# ProProject_PetCareSTM32_MiniSTM32_2024-0.net
KiCad netlist of a schematic drawn in EasyEDA Pro
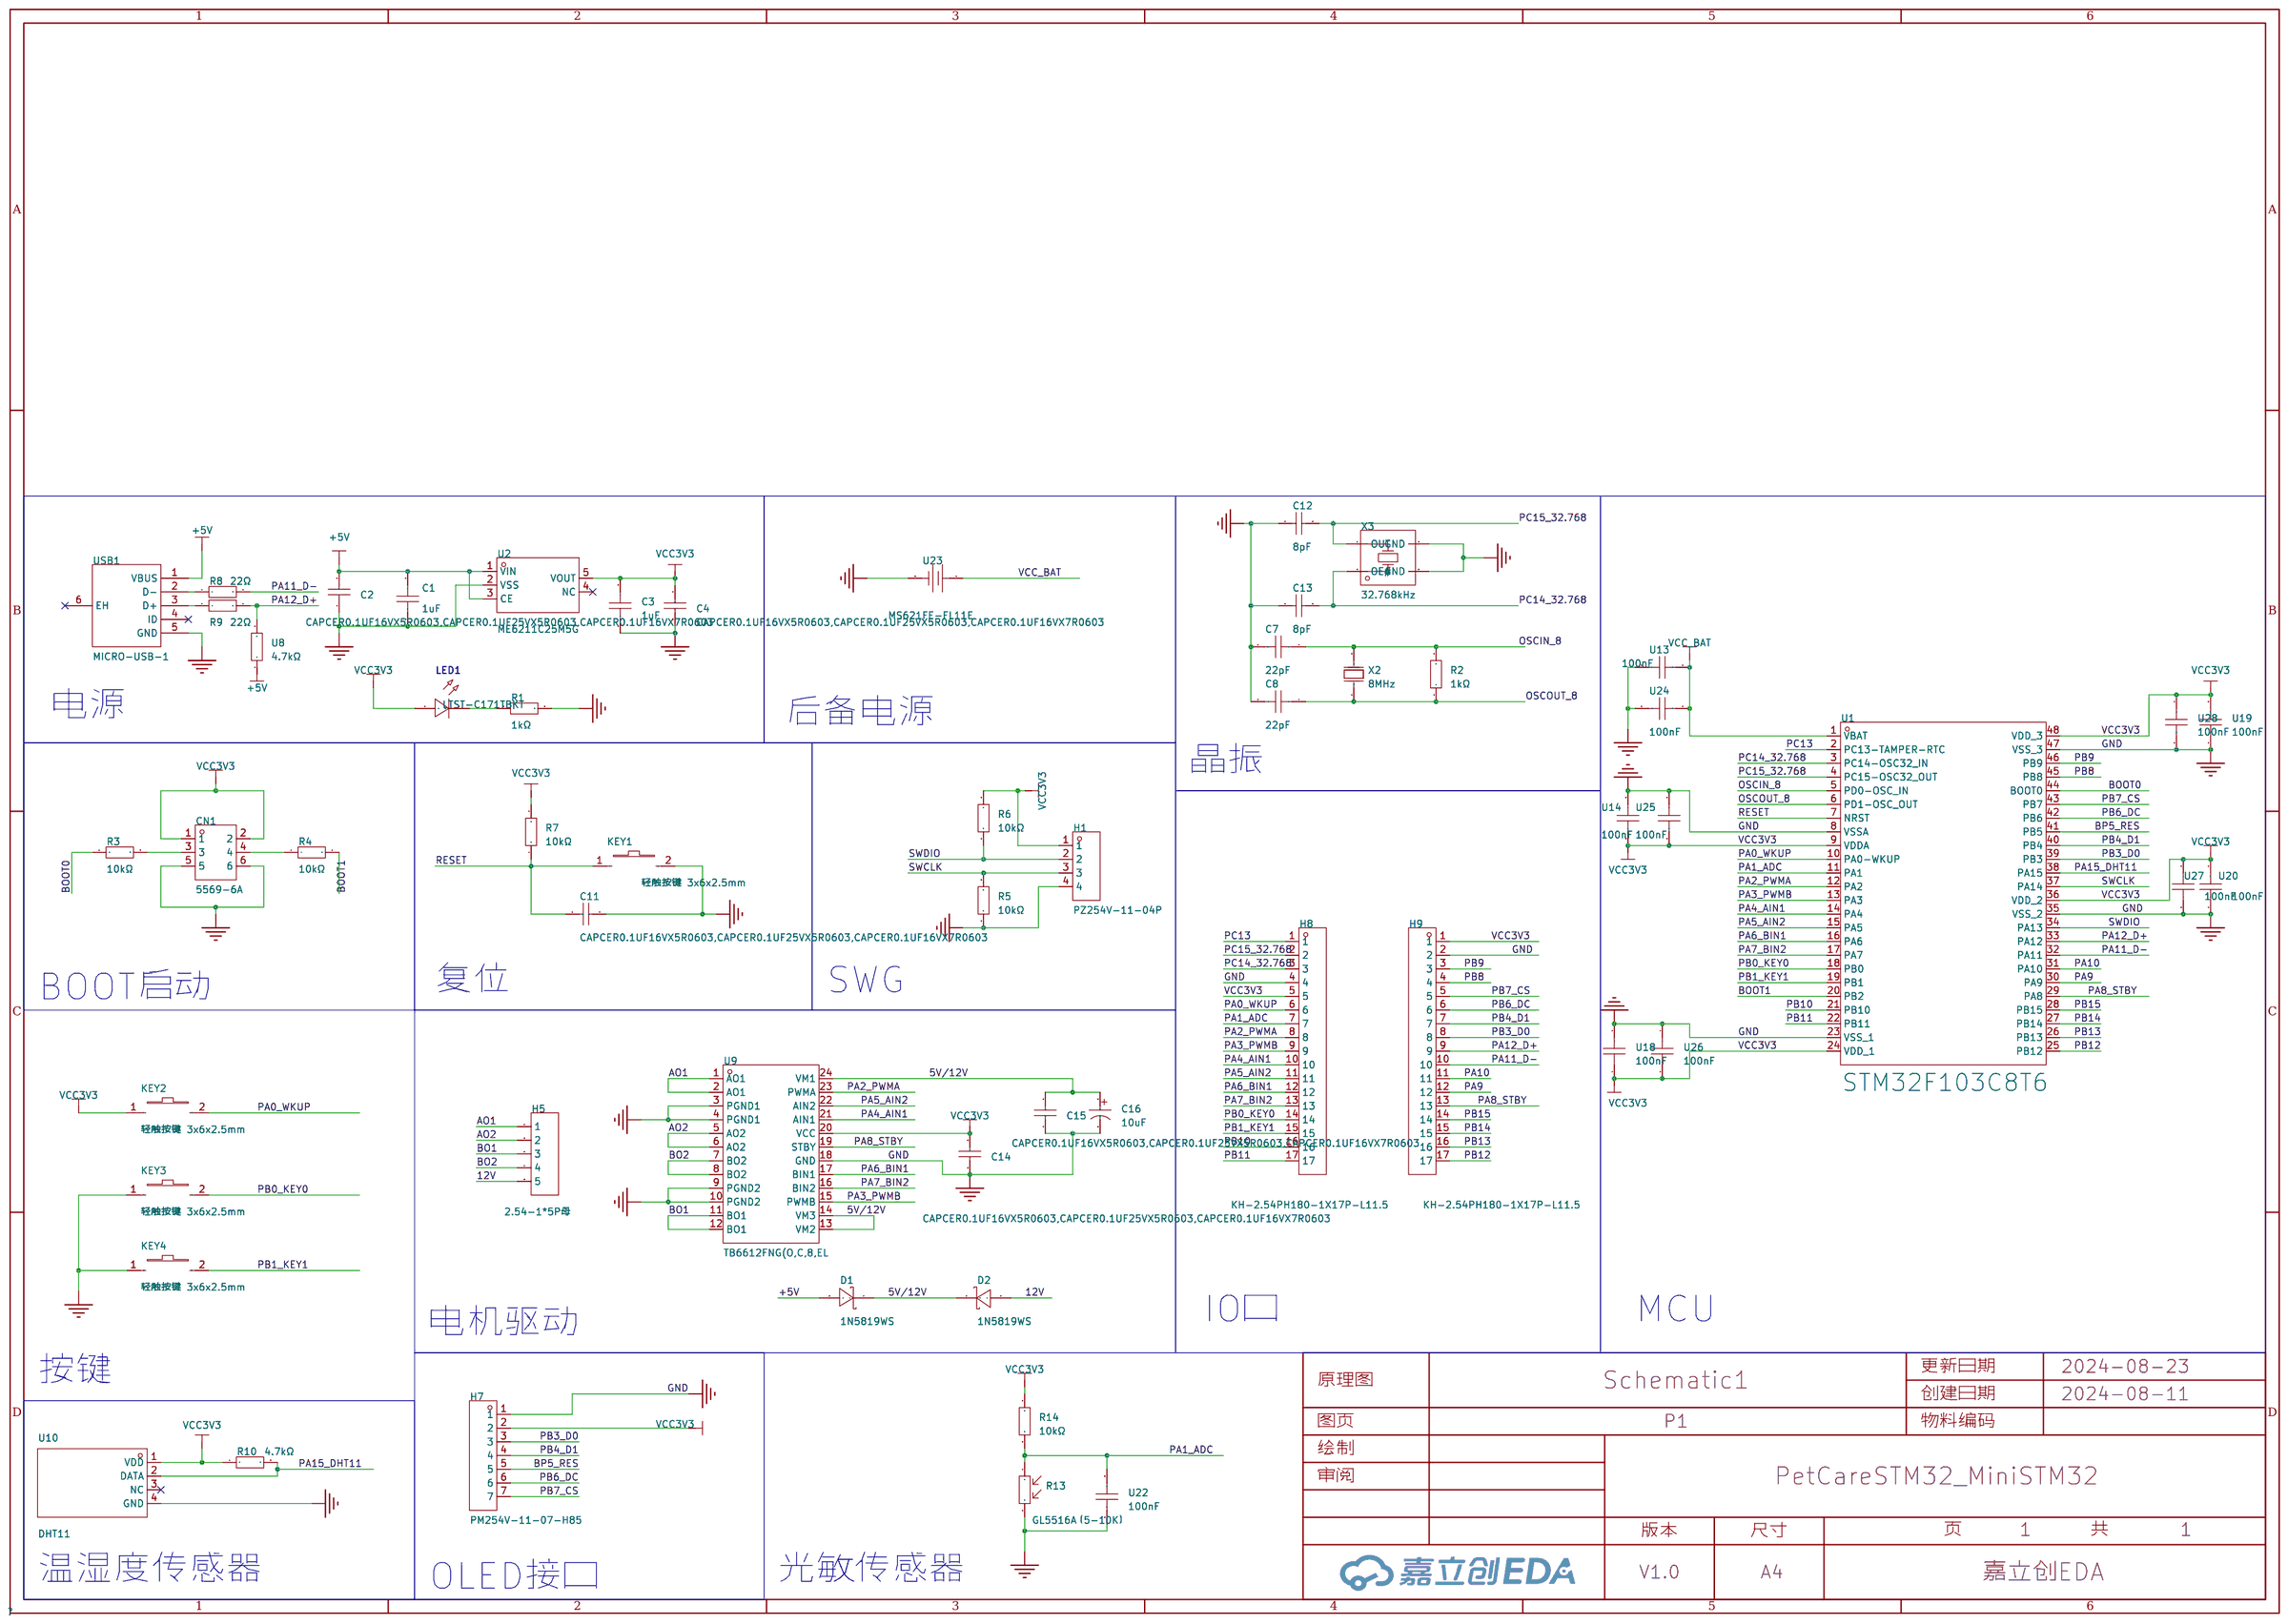
[diagram p0: schematic sheet]

(export (version "E")
  (design (tool "Eeschema 10.0.6"))
  (components
    (comp (ref "C1")
      (value "1uF")
      (footprint "easyedapro:C0603")
      (description "容值:1uF;精度:±10%;额定电压:50V;材质(温度系数):X5R;")
      (fields
        (field (name "Manufacturer Part") "CL10A105KB8NNNC")
        (field (name "Manufacturer") "SAMSUNG(三星)")
      )
      (libsource (lib "easyedapro") (part "CL10A105KB8NNNC"))
    )
    (comp (ref "C2")
      (value "CAPCER0.1UF16VX5R0603,CAPCER0.1UF25VX5R0603,CAPCER0.1UF16VX7R0603")
      (footprint "easyedapro:C0603")
      (libsource (lib "easyedapro") (part "CAPCER0.1UF16VX5R0603,CAPCER0.1UF25VX5R0603,CAPCER0.1UF16VX7R0603"))
    )
    (comp (ref "C3")
      (value "1uF")
      (footprint "easyedapro:C0603")
      (description "容值:1uF;精度:±10%;额定电压:50V;材质(温度系数):X5R;")
      (fields
        (field (name "Manufacturer Part") "CL10A105KB8NNNC")
        (field (name "Manufacturer") "SAMSUNG(三星)")
      )
      (libsource (lib "easyedapro") (part "CL10A105KB8NNNC"))
    )
    (comp (ref "C4")
      (value "CAPCER0.1UF16VX5R0603,CAPCER0.1UF25VX5R0603,CAPCER0.1UF16VX7R0603")
      (footprint "easyedapro:C0603")
      (libsource (lib "easyedapro") (part "CAPCER0.1UF16VX5R0603,CAPCER0.1UF25VX5R0603,CAPCER0.1UF16VX7R0603"))
    )
    (comp (ref "C7")
      (value "22pF")
      (footprint "easyedapro:C0603")
      (description "容值:22pF;精度:±5%;额定电压:50V;材质(温度系数):C0G;")
      (fields
        (field (name "Manufacturer Part") "CL10C220JB81PNC")
        (field (name "Manufacturer") "SAMSUNG(三星)")
      )
      (libsource (lib "easyedapro") (part "CL10C220JB81PNC"))
    )
    (comp (ref "C8")
      (value "22pF")
      (footprint "easyedapro:C0603")
      (description "容值:22pF;精度:±5%;额定电压:50V;材质(温度系数):C0G;")
      (fields
        (field (name "Manufacturer Part") "CL10C220JB81PNC")
        (field (name "Manufacturer") "SAMSUNG(三星)")
      )
      (libsource (lib "easyedapro") (part "CL10C220JB81PNC"))
    )
    (comp (ref "C11")
      (value "CAPCER0.1UF16VX5R0603,CAPCER0.1UF25VX5R0603,CAPCER0.1UF16VX7R0603")
      (footprint "easyedapro:C0603")
      (libsource (lib "easyedapro") (part "CAPCER0.1UF16VX5R0603,CAPCER0.1UF25VX5R0603,CAPCER0.1UF16VX7R0603"))
    )
    (comp (ref "C12")
      (value "8pF")
      (footprint "easyedapro:C0603")
      (description "容值:8pF;额定电压:50V;材质(温度系数):C0G;")
      (fields (field (name "Manufacturer Part") "0603CG8R0C500NT") (field (name "Manufacturer") "FH(风华)"))
      (libsource (lib "easyedapro") (part "0603CG8R0C500NT_C36508"))
    )
    (comp (ref "C13")
      (value "8pF")
      (footprint "easyedapro:C0603")
      (description "容值:8pF;额定电压:50V;材质(温度系数):C0G;")
      (fields (field (name "Manufacturer Part") "0603CG8R0C500NT") (field (name "Manufacturer") "FH(风华)"))
      (libsource (lib "easyedapro") (part "0603CG8R0C500NT_C36508"))
    )
    (comp (ref "C14")
      (value "CAPCER0.1UF16VX5R0603,CAPCER0.1UF25VX5R0603,CAPCER0.1UF16VX7R0603")
      (footprint "easyedapro:C0603")
      (libsource (lib "easyedapro") (part "CAPCER0.1UF16VX5R0603,CAPCER0.1UF25VX5R0603,CAPCER0.1UF16VX7R0603"))
    )
    (comp (ref "C15")
      (value "CAPCER0.1UF16VX5R0603,CAPCER0.1UF25VX5R0603,CAPCER0.1UF16VX7R0603")
      (footprint "easyedapro:C0603")
      (libsource (lib "easyedapro") (part "CAPCER0.1UF16VX5R0603,CAPCER0.1UF25VX5R0603,CAPCER0.1UF16VX7R0603"))
    )
    (comp (ref "C16")
      (value "10uF")
      (footprint "easyedapro:CAP-TH_BD5.0-P2.00-D0.8-FD")
      (description "容值:10uF;精度:±20%;额定电压:25V;")
      (fields (field (name "Manufacturer Part") "KF100M025C110A") (field (name "Manufacturer") "CapXon(丰宾)"))
      (libsource (lib "easyedapro") (part "KF100M025C110A"))
    )
    (comp (ref "CN1")
      (value "5569-6A")
      (footprint "easyedapro:CONN-TH_6P-P4.20_5569-6A-1")
      (libsource (lib "easyedapro") (part "5569-6A"))
    )
    (comp (ref "D1")
      (value "1N5819WS")
      (footprint "easyedapro:SOD-323_L1.8-W1.3-LS2.5-RD")
      (description "正向压降(Vf):600mV@1A;直流反向耐压(Vr):40V;平均整流电流(Io):1A;")
      (fields (field (name "Manufacturer") "Hottech(合科泰)"))
      (libsource (lib "easyedapro") (part "1N5819WS"))
    )
    (comp (ref "D2")
      (value "1N5819WS")
      (footprint "easyedapro:SOD-323_L1.8-W1.3-LS2.5-RD")
      (description "正向压降(Vf):600mV@1A;直流反向耐压(Vr):40V;平均整流电流(Io):1A;")
      (fields (field (name "Manufacturer") "Hottech(合科泰)"))
      (libsource (lib "easyedapro") (part "1N5819WS"))
    )
    (comp (ref "H1")
      (value "PZ254V-11-04P")
      (footprint "easyedapro:HDR-TH_4P-P2.54-V-M")
      (fields (field (name "Manufacturer") "XFCN(兴飞)"))
      (libsource (lib "easyedapro") (part "PZ254V-11-04P_C2691448"))
    )
    (comp (ref "H5")
      (value "2.54-1*5P母")
      (footprint "easyedapro:HDR-TH_5P-P2.54-V-F")
      (description "插孔结构:1x5P;间距:2.54mm;行距:-;安装类型:直插;排数:单排;总孔位数:5P;塑高:-;触头材质:-;触头镀层:-;")
      (fields (field (name "Manufacturer") "BOOMELE(博穆精密)"))
      (libsource (lib "easyedapro") (part "Header-Female-2.54_1x5"))
    )
    (comp (ref "H7")
      (value "PM254V-11-07-H85")
      (footprint "easyedapro:HDR-TH_7P-P2.54-V-F")
      (fields (field (name "Manufacturer") "XFCN(兴飞)"))
      (libsource (lib "easyedapro") (part "PM254V-11-07-H85"))
    )
    (comp (ref "H8")
      (value "KH-2.54PH180-1X17P-L11.5")
      (footprint "easyedapro:HDR-TH_17P-P2.54-V-M")
      (fields (field (name "Manufacturer") "kinghelm(金航标)"))
      (libsource (lib "easyedapro") (part "KH-2.54PH180-1X17P-L11.5"))
    )
    (comp (ref "H9")
      (value "KH-2.54PH180-1X17P-L11.5")
      (footprint "easyedapro:HDR-TH_17P-P2.54-V-M")
      (fields (field (name "Manufacturer") "kinghelm(金航标)"))
      (libsource (lib "easyedapro") (part "KH-2.54PH180-1X17P-L11.5"))
    )
    (comp (ref "KEY1")
      (value "轻触按键 3x6x2.5mm")
      (footprint "easyedapro:SW-SMD_L6.0-W3.6-LS8.0")
      (libsource (lib "easyedapro") (part "3x6x2.5mm"))
    )
    (comp (ref "KEY2")
      (value "轻触按键 3x6x2.5mm")
      (footprint "easyedapro:SW-SMD_L6.0-W3.6-LS8.0")
      (libsource (lib "easyedapro") (part "3x6x2.5mm"))
    )
    (comp (ref "KEY3")
      (value "轻触按键 3x6x2.5mm")
      (footprint "easyedapro:SW-SMD_L6.0-W3.6-LS8.0")
      (libsource (lib "easyedapro") (part "3x6x2.5mm"))
    )
    (comp (ref "KEY4")
      (value "轻触按键 3x6x2.5mm")
      (footprint "easyedapro:SW-SMD_L6.0-W3.6-LS8.0")
      (libsource (lib "easyedapro") (part "3x6x2.5mm"))
    )
    (comp (ref "LED1")
      (value "LTST-C171TBKT")
      (footprint "easyedapro:LED_0805")
      (fields (field (name "Manufacturer") "LITEON(光宝)"))
      (libsource (lib "easyedapro") (part "LED_B"))
    )
    (comp (ref "R1")
      (value "1kΩ")
      (footprint "easyedapro:R0603")
      (description "电阻类型:厚膜电阻;阻值:1kΩ;精度:±1%;功率:100mW;最大工作电压:75V;温度系数:±100ppm/°C;")
      (fields (field (name "Manufacturer Part") "RC0603FR-071KL") (field (name "Manufacturer") "YAGEO(国巨)"))
      (libsource (lib "easyedapro") (part "RC0603FR-071KL"))
    )
    (comp (ref "R2")
      (value "1kΩ")
      (footprint "easyedapro:R0603")
      (description "电阻类型:厚膜电阻;阻值:1kΩ;精度:±0.5%;功率:100mW;最大工作电压:75V;温度系数:±100ppm/°C;")
      (fields
        (field (name "Manufacturer Part") "0603WAD1001T5E")
        (field (name "Manufacturer") "UNI-ROYAL(厚声)")
      )
      (libsource (lib "easyedapro") (part "0603WAD1001T5E"))
    )
    (comp (ref "R3")
      (value "10kΩ")
      (footprint "easyedapro:R0603")
      (description "电阻类型:厚膜电阻;阻值:10kΩ;精度:±1%;功率:100mW;最大工作电压:75V;温度系数:±100ppm/°C;")
      (fields
        (field (name "Manufacturer Part") "0603WAF1002T5E")
        (field (name "Manufacturer") "UNI-ROYAL(厚声)")
      )
      (libsource (lib "easyedapro") (part "0603WAF1002T5E"))
    )
    (comp (ref "R4")
      (value "10kΩ")
      (footprint "easyedapro:R0603")
      (description "电阻类型:厚膜电阻;阻值:10kΩ;精度:±1%;功率:100mW;最大工作电压:75V;温度系数:±100ppm/°C;")
      (fields
        (field (name "Manufacturer Part") "0603WAF1002T5E")
        (field (name "Manufacturer") "UNI-ROYAL(厚声)")
      )
      (libsource (lib "easyedapro") (part "0603WAF1002T5E"))
    )
    (comp (ref "R5")
      (value "10kΩ")
      (footprint "easyedapro:R0603")
      (description "电阻类型:厚膜电阻;阻值:10kΩ;精度:±1%;功率:100mW;最大工作电压:75V;温度系数:±100ppm/°C;")
      (fields
        (field (name "Manufacturer Part") "0603WAF1002T5E")
        (field (name "Manufacturer") "UNI-ROYAL(厚声)")
      )
      (libsource (lib "easyedapro") (part "0603WAF1002T5E"))
    )
    (comp (ref "R6")
      (value "10kΩ")
      (footprint "easyedapro:R0603")
      (description "电阻类型:厚膜电阻;阻值:10kΩ;精度:±1%;功率:100mW;最大工作电压:75V;温度系数:±100ppm/°C;")
      (fields
        (field (name "Manufacturer Part") "0603WAF1002T5E")
        (field (name "Manufacturer") "UNI-ROYAL(厚声)")
      )
      (libsource (lib "easyedapro") (part "0603WAF1002T5E"))
    )
    (comp (ref "R7")
      (value "10kΩ")
      (footprint "easyedapro:R0603")
      (description "电阻类型:厚膜电阻;阻值:10kΩ;精度:±1%;功率:100mW;最大工作电压:75V;温度系数:±100ppm/°C;")
      (fields
        (field (name "Manufacturer Part") "0603WAF1002T5E")
        (field (name "Manufacturer") "UNI-ROYAL(厚声)")
      )
      (libsource (lib "easyedapro") (part "0603WAF1002T5E"))
    )
    (comp (ref "R8")
      (value "22Ω")
      (footprint "easyedapro:R0805")
      (description "电阻类型:薄膜电阻;阻值:22Ω;精度:±1%;功率:250mW;最大工作电压:150V;温度系数:±25ppm/°C;")
      (fields
        (field (name "Manufacturer Part") "TC0525F220JT5E")
        (field (name "Manufacturer") "UNI-ROYAL(厚声)")
      )
      (libsource (lib "easyedapro") (part "TC0525F220JT5E"))
    )
    (comp (ref "R9")
      (value "22Ω")
      (footprint "easyedapro:R0805")
      (description "电阻类型:薄膜电阻;阻值:22Ω;精度:±1%;功率:250mW;最大工作电压:150V;温度系数:±25ppm/°C;")
      (fields
        (field (name "Manufacturer Part") "TC0525F220JT5E")
        (field (name "Manufacturer") "UNI-ROYAL(厚声)")
      )
      (libsource (lib "easyedapro") (part "TC0525F220JT5E"))
    )
    (comp (ref "R10")
      (value "4.7kΩ")
      (footprint "easyedapro:R1206")
      (description "电阻类型:厚膜电阻;阻值:4.7kΩ;精度:±1%;功率:250mW;最大工作电压:200V;温度系数:±100ppm/°C;")
      (fields
        (field (name "Manufacturer Part") "1206W4F4701T5E")
        (field (name "Manufacturer") "UNI-ROYAL(厚声)")
      )
      (libsource (lib "easyedapro") (part "1206W4F4701T5E"))
    )
    (comp (ref "R13")
      (value "GL5516A（5-10K）")
      (footprint "easyedapro:RES-TH_L5.1-W4.3-P3.40_GL55")
      (description "暗电阻:200kΩ;亮电阻 @ 10Lux:5kΩ~10kΩ;光谱峰值(波长):540nm;")
      (fields (field (name "Manufacturer") "JCHL(晶创和立)"))
      (libsource (lib "easyedapro") (part "GL5516A(5-10K)"))
    )
    (comp (ref "R14")
      (value "10kΩ")
      (footprint "easyedapro:R0603")
      (description "电阻类型:厚膜电阻;阻值:10kΩ;精度:±1%;功率:100mW;最大工作电压:75V;温度系数:±100ppm/°C;")
      (fields
        (field (name "Manufacturer Part") "0603WAF1002T5E")
        (field (name "Manufacturer") "UNI-ROYAL(厚声)")
      )
      (libsource (lib "easyedapro") (part "0603WAF1002T5E"))
    )
    (comp (ref "U1")
      (value "STM32F103C8T6")
      (footprint "easyedapro:LQFP-48_L7.0-W7.0-P0.50-LS9.0-BL")
      (description "CPU内核:ARM-M3;程序存储容量:64KB;RAM总容量:20KB;GPIO端口数量:37;工作电压范围:2V~3.6V;CPU最大主频:72MHz;程序存储器类型:FLASH;")
      (fields (field (name "Manufacturer") "ST(意法半导体)"))
      (libsource (lib "easyedapro") (part "STM32F103C8T6"))
    )
    (comp (ref "U2")
      (value "ME6211C25M5G")
      (footprint "easyedapro:SOT-23-5_L2.9-W1.7-P0.95-LS2.8-BL")
      (fields (field (name "Manufacturer") "MICRONE(南京微盟)"))
      (libsource (lib "easyedapro") (part "ME6211C25M5G"))
    )
    (comp (ref "U8")
      (value "4.7kΩ")
      (footprint "easyedapro:R0603")
      (description "电阻类型:薄膜电阻;阻值:4.7kΩ;精度:±1%;功率:100mW;最大工作电压:75V;温度系数:±50ppm/°C;")
      (fields (field (name "Manufacturer Part") "AR03FTDX4701A") (field (name "Manufacturer") "Viking(光颉)"))
      (libsource (lib "easyedapro") (part "AR03FTDX4701A"))
    )
    (comp (ref "U9")
      (value "TB6612FNG(O,C,8,EL")
      (footprint "easyedapro:SSOP-24_L8.4-W5.8-P0.65-LS7.8-BL")
      (description "双直流电机驱动器集成电路")
      (fields (field (name "Manufacturer") "TOSHIBA(东芝)"))
      (libsource (lib "easyedapro") (part "TB6612FNG(O,C,8,EL"))
    )
    (comp (ref "U10")
      (value "DHT11")
      (footprint "easyedapro:SENSOR-TH_DHT11")
      (description "新款电容式数字温湿度传感器,老款已停产16.1x12.6x5.8mm")
      (fields (field (name "Manufacturer") "广州奥松"))
      (libsource (lib "easyedapro") (part "DHT11"))
    )
    (comp (ref "U13")
      (value "100nF")
      (footprint "easyedapro:C0603")
      (description "容值:100nF;精度:±10%;额定电压:50V;材质(温度系数):X7R;")
      (fields
        (field (name "Manufacturer Part") "CGA0603X7R104K500JT")
        (field (name "Manufacturer") "HRE(芯声)")
      )
      (libsource (lib "easyedapro") (part "CGA0603X7R104K500JT"))
    )
    (comp (ref "U14")
      (value "100nF")
      (footprint "easyedapro:C0603")
      (description "容值:100nF;精度:±10%;额定电压:50V;材质(温度系数):X7R;")
      (fields
        (field (name "Manufacturer Part") "CGA0603X7R104K500JT")
        (field (name "Manufacturer") "HRE(芯声)")
      )
      (libsource (lib "easyedapro") (part "CGA0603X7R104K500JT"))
    )
    (comp (ref "U18")
      (value "100nF")
      (footprint "easyedapro:C0603")
      (description "容值:100nF;精度:±10%;额定电压:50V;材质(温度系数):X7R;")
      (fields
        (field (name "Manufacturer Part") "CGA0603X7R104K500JT")
        (field (name "Manufacturer") "HRE(芯声)")
      )
      (libsource (lib "easyedapro") (part "CGA0603X7R104K500JT"))
    )
    (comp (ref "U19")
      (value "100nF")
      (footprint "easyedapro:C0603")
      (description "容值:100nF;精度:±10%;额定电压:50V;材质(温度系数):X7R;")
      (fields
        (field (name "Manufacturer Part") "CGA0603X7R104K500JT")
        (field (name "Manufacturer") "HRE(芯声)")
      )
      (libsource (lib "easyedapro") (part "CGA0603X7R104K500JT"))
    )
    (comp (ref "U20")
      (value "100nF")
      (footprint "easyedapro:C0603")
      (description "容值:100nF;精度:±10%;额定电压:50V;材质(温度系数):X7R;")
      (fields
        (field (name "Manufacturer Part") "CGA0603X7R104K500JT")
        (field (name "Manufacturer") "HRE(芯声)")
      )
      (libsource (lib "easyedapro") (part "CGA0603X7R104K500JT"))
    )
    (comp (ref "U22")
      (value "100nF")
      (footprint "easyedapro:C0603")
      (description "容值:100nF;精度:±10%;额定电压:50V;材质(温度系数):X7R;")
      (fields
        (field (name "Manufacturer Part") "CGA0603X7R104K500JT")
        (field (name "Manufacturer") "HRE(芯声)")
      )
      (libsource (lib "easyedapro") (part "CGA0603X7R104K500JT"))
    )
    (comp (ref "U23")
      (value "MS621FE-FL11E")
      (footprint "easyedapro:BAT-SMD_FL11E")
      (description "FL11E 3.3V可充电纽扣电池 5.5mAH")
      (fields (field (name "Manufacturer") "Seiko(精工)"))
      (libsource (lib "easyedapro") (part "MS621FE-FL11E"))
    )
    (comp (ref "U24")
      (value "100nF")
      (footprint "easyedapro:C0603")
      (description "容值:100nF;精度:±10%;额定电压:50V;材质(温度系数):X7R;")
      (fields
        (field (name "Manufacturer Part") "CGA0603X7R104K500JT")
        (field (name "Manufacturer") "HRE(芯声)")
      )
      (libsource (lib "easyedapro") (part "CGA0603X7R104K500JT"))
    )
    (comp (ref "U25")
      (value "100nF")
      (footprint "easyedapro:C0603")
      (description "容值:100nF;精度:±10%;额定电压:50V;材质(温度系数):X7R;")
      (fields
        (field (name "Manufacturer Part") "CGA0603X7R104K500JT")
        (field (name "Manufacturer") "HRE(芯声)")
      )
      (libsource (lib "easyedapro") (part "CGA0603X7R104K500JT"))
    )
    (comp (ref "U26")
      (value "100nF")
      (footprint "easyedapro:C0603")
      (description "容值:100nF;精度:±10%;额定电压:50V;材质(温度系数):X7R;")
      (fields
        (field (name "Manufacturer Part") "CGA0603X7R104K500JT")
        (field (name "Manufacturer") "HRE(芯声)")
      )
      (libsource (lib "easyedapro") (part "CGA0603X7R104K500JT"))
    )
    (comp (ref "U27")
      (value "100nF")
      (footprint "easyedapro:C0603")
      (description "容值:100nF;精度:±10%;额定电压:50V;材质(温度系数):X7R;")
      (fields
        (field (name "Manufacturer Part") "CGA0603X7R104K500JT")
        (field (name "Manufacturer") "HRE(芯声)")
      )
      (libsource (lib "easyedapro") (part "CGA0603X7R104K500JT"))
    )
    (comp (ref "U28")
      (value "100nF")
      (footprint "easyedapro:C0603")
      (description "容值:100nF;精度:±10%;额定电压:50V;材质(温度系数):X7R;")
      (fields
        (field (name "Manufacturer Part") "CGA0603X7R104K500JT")
        (field (name "Manufacturer") "HRE(芯声)")
      )
      (libsource (lib "easyedapro") (part "CGA0603X7R104K500JT"))
    )
    (comp (ref "USB1")
      (value "MICRO-USB-1")
      (footprint "easyedapro:MICRO-USB-SMD_C9900008946")
      (libsource (lib "easyedapro") (part "MICRO-USB-1"))
    )
    (comp (ref "X2")
      (value "8MHz")
      (footprint "easyedapro:OSC-SMD_L5.0-W3.2")
      (description "晶振类型:贴片晶振;频率:8MHz;常温频差:±20ppm;外接负载电容:18pF;频率稳定度(全温):±30ppm;")
      (fields
        (field (name "Manufacturer Part") "ABM3-8.000MHZ-D2Y-T")
        (field (name "Manufacturer") "ABRACON")
      )
      (libsource (lib "easyedapro") (part "ABM3-8.000MHZ-D2Y-T"))
    )
    (comp (ref "X3")
      (value "32.768kHz")
      (footprint "easyedapro:CRYSTAL-SMD_4P-L8.0-W3.8-BL")
      (description "晶振类型:-;频率:32.768kHz;常温频差:±20ppm;外接负载电容:12.5pF;频率稳定度(全温):-;")
      (fields (field (name "Manufacturer Part") "ABS25-32.768KHZ-T") (field (name "Manufacturer") "ABRACON"))
      (libsource (lib "easyedapro") (part "ABS25-32.768KHZ-T"))
    )
  )
  (nets
    (net (code "1") (name "+5V") (class "Default")
      (node (ref "C1") (pin "2") (pinfunction "2_2") (pintype "unspecified"))
      (node (ref "C2") (pin "2") (pinfunction "2_2") (pintype "input"))
      (node (ref "D1") (pin "2") (pinfunction "A_2") (pintype "unspecified"))
      (node (ref "U2") (pin "1") (pinfunction "VIN_1") (pintype "unspecified"))
      (node (ref "U2") (pin "3") (pinfunction "CE_3") (pintype "unspecified"))
      (node (ref "U8") (pin "1") (pinfunction "1_1") (pintype "unspecified"))
      (node (ref "USB1") (pin "1") (pinfunction "VBUS_1") (pintype "input"))
    )
    (net (code "2") (name "/5V{slash}12V") (class "Default")
      (node (ref "C15") (pin "2") (pinfunction "2_2") (pintype "input"))
      (node (ref "C16") (pin "1") (pinfunction "1_1") (pintype "input"))
      (node (ref "D1") (pin "1") (pinfunction "K_1") (pintype "unspecified"))
      (node (ref "D2") (pin "1") (pinfunction "K_1") (pintype "unspecified"))
      (node (ref "U9") (pin "13") (pinfunction "VM2_13") (pintype "unspecified"))
      (node (ref "U9") (pin "14") (pinfunction "VM3_14") (pintype "unspecified"))
      (node (ref "U9") (pin "24") (pinfunction "VM1_24") (pintype "unspecified"))
    )
    (net (code "3") (name "/12V") (class "Default")
      (node (ref "D2") (pin "2") (pinfunction "A_2") (pintype "unspecified"))
      (node (ref "H5") (pin "5") (pinfunction "5_5") (pintype "input"))
    )
    (net (code "4") (name "/AO1") (class "Default")
      (node (ref "H5") (pin "1") (pinfunction "1_1") (pintype "input"))
      (node (ref "U9") (pin "1") (pinfunction "AO1_1") (pintype "unspecified"))
      (node (ref "U9") (pin "2") (pinfunction "AO1_2") (pintype "unspecified"))
    )
    (net (code "5") (name "/AO2") (class "Default")
      (node (ref "H5") (pin "2") (pinfunction "2_2") (pintype "input"))
      (node (ref "U9") (pin "5") (pinfunction "AO2_5") (pintype "unspecified"))
      (node (ref "U9") (pin "6") (pinfunction "AO2_6") (pintype "unspecified"))
    )
    (net (code "6") (name "/BO1") (class "Default")
      (node (ref "H5") (pin "3") (pinfunction "3_3") (pintype "input"))
      (node (ref "U9") (pin "11") (pinfunction "BO1_11") (pintype "unspecified"))
      (node (ref "U9") (pin "12") (pinfunction "BO1_12") (pintype "unspecified"))
    )
    (net (code "7") (name "/BO2") (class "Default")
      (node (ref "H5") (pin "4") (pinfunction "4_4") (pintype "input"))
      (node (ref "U9") (pin "7") (pinfunction "BO2_7") (pintype "unspecified"))
      (node (ref "U9") (pin "8") (pinfunction "BO2_8") (pintype "unspecified"))
    )
    (net (code "8") (name "/BOOT0") (class "Default")
      (node (ref "R3") (pin "1") (pinfunction "1_1") (pintype "input"))
      (node (ref "U1") (pin "44") (pinfunction "BOOT0_44") (pintype "unspecified"))
    )
    (net (code "9") (name "/BOOT1") (class "Default")
      (node (ref "R4") (pin "2") (pinfunction "2_2") (pintype "input"))
      (node (ref "U1") (pin "20") (pinfunction "PB2_20") (pintype "unspecified"))
    )
    (net (code "10") (name "/BP5_RES") (class "Default")
      (node (ref "H7") (pin "5") (pinfunction "5_5") (pintype "unspecified"))
      (node (ref "U1") (pin "41") (pinfunction "PB5_41") (pintype "unspecified"))
    )
    (net (code "11") (name "/OSCIN_8") (class "Default")
      (node (ref "C7") (pin "1") (pinfunction "1_1") (pintype "unspecified"))
      (node (ref "R2") (pin "2") (pinfunction "2_2") (pintype "input"))
      (node (ref "U1") (pin "5") (pinfunction "PD0-OSC_IN_5") (pintype "unspecified"))
      (node (ref "X2") (pin "2") (pinfunction "OSC2_2") (pintype "input"))
    )
    (net (code "12") (name "/OSCOUT_8") (class "Default")
      (node (ref "C8") (pin "1") (pinfunction "1_1") (pintype "unspecified"))
      (node (ref "R2") (pin "1") (pinfunction "1_1") (pintype "input"))
      (node (ref "U1") (pin "6") (pinfunction "PD1-OSC_OUT_6") (pintype "unspecified"))
      (node (ref "X2") (pin "1") (pinfunction "OSC1_1") (pintype "input"))
    )
    (net (code "13") (name "/PA0_WKUP") (class "Default")
      (node (ref "H8") (pin "6") (pinfunction "6_6") (pintype "unspecified"))
      (node (ref "KEY2") (pin "2") (pinfunction "2_2") (pintype "input"))
      (node (ref "U1") (pin "10") (pinfunction "PA0-WKUP_10") (pintype "unspecified"))
    )
    (net (code "14") (name "/PA1_ADC") (class "Default")
      (node (ref "H8") (pin "7") (pinfunction "7_7") (pintype "unspecified"))
      (node (ref "R13") (pin "1") (pinfunction "1_1") (pintype "input"))
      (node (ref "R14") (pin "1") (pinfunction "1_1") (pintype "input"))
      (node (ref "U1") (pin "11") (pinfunction "PA1_11") (pintype "unspecified"))
      (node (ref "U22") (pin "2") (pinfunction "2_2") (pintype "unspecified"))
    )
    (net (code "15") (name "/PA2_PWMA") (class "Default")
      (node (ref "H8") (pin "8") (pinfunction "8_8") (pintype "unspecified"))
      (node (ref "U1") (pin "12") (pinfunction "PA2_12") (pintype "unspecified"))
      (node (ref "U9") (pin "23") (pinfunction "PWMA_23") (pintype "unspecified"))
    )
    (net (code "16") (name "/PA3_PWMB") (class "Default")
      (node (ref "H8") (pin "9") (pinfunction "9_9") (pintype "unspecified"))
      (node (ref "U1") (pin "13") (pinfunction "PA3_13") (pintype "unspecified"))
      (node (ref "U9") (pin "15") (pinfunction "PWMB_15") (pintype "unspecified"))
    )
    (net (code "17") (name "/PA4_AIN1") (class "Default")
      (node (ref "H8") (pin "10") (pinfunction "10_10") (pintype "unspecified"))
      (node (ref "U1") (pin "14") (pinfunction "PA4_14") (pintype "unspecified"))
      (node (ref "U9") (pin "21") (pinfunction "AIN1_21") (pintype "unspecified"))
    )
    (net (code "18") (name "/PA5_AIN2") (class "Default")
      (node (ref "H8") (pin "11") (pinfunction "11_11") (pintype "unspecified"))
      (node (ref "U1") (pin "15") (pinfunction "PA5_15") (pintype "unspecified"))
      (node (ref "U9") (pin "22") (pinfunction "AIN2_22") (pintype "unspecified"))
    )
    (net (code "19") (name "/PA6_BIN1") (class "Default")
      (node (ref "H8") (pin "12") (pinfunction "12_12") (pintype "unspecified"))
      (node (ref "U1") (pin "16") (pinfunction "PA6_16") (pintype "unspecified"))
      (node (ref "U9") (pin "17") (pinfunction "BIN1_17") (pintype "unspecified"))
    )
    (net (code "20") (name "/PA7_BIN2") (class "Default")
      (node (ref "H8") (pin "13") (pinfunction "13_13") (pintype "unspecified"))
      (node (ref "U1") (pin "17") (pinfunction "PA7_17") (pintype "unspecified"))
      (node (ref "U9") (pin "16") (pinfunction "BIN2_16") (pintype "unspecified"))
    )
    (net (code "21") (name "/PA8_STBY") (class "Default")
      (node (ref "H9") (pin "13") (pinfunction "13_13") (pintype "unspecified"))
      (node (ref "U1") (pin "29") (pinfunction "PA8_29") (pintype "unspecified"))
      (node (ref "U9") (pin "19") (pinfunction "STBY_19") (pintype "unspecified"))
    )
    (net (code "22") (name "/PA9") (class "Default")
      (node (ref "H9") (pin "12") (pinfunction "12_12") (pintype "unspecified"))
      (node (ref "U1") (pin "30") (pinfunction "PA9_30") (pintype "unspecified"))
    )
    (net (code "23") (name "/PA10") (class "Default")
      (node (ref "H9") (pin "11") (pinfunction "11_11") (pintype "unspecified"))
      (node (ref "U1") (pin "31") (pinfunction "PA10_31") (pintype "unspecified"))
    )
    (net (code "24") (name "/PA11_D-") (class "Default")
      (node (ref "H9") (pin "10") (pinfunction "10_10") (pintype "unspecified"))
      (node (ref "R8") (pin "2") (pinfunction "2_2") (pintype "input"))
      (node (ref "U1") (pin "32") (pinfunction "PA11_32") (pintype "unspecified"))
    )
    (net (code "25") (name "/PA12_D+") (class "Default")
      (node (ref "H9") (pin "9") (pinfunction "9_9") (pintype "unspecified"))
      (node (ref "R9") (pin "2") (pinfunction "2_2") (pintype "input"))
      (node (ref "U1") (pin "33") (pinfunction "PA12_33") (pintype "unspecified"))
      (node (ref "U8") (pin "2") (pinfunction "2_2") (pintype "unspecified"))
    )
    (net (code "26") (name "/PA15_DHT11") (class "Default")
      (node (ref "R10") (pin "2") (pinfunction "2_2") (pintype "input"))
      (node (ref "U1") (pin "38") (pinfunction "PA15_38") (pintype "unspecified"))
      (node (ref "U10") (pin "2") (pinfunction "DATA_2") (pintype "unspecified"))
    )
    (net (code "27") (name "/PB0_KEY0") (class "Default")
      (node (ref "H8") (pin "14") (pinfunction "14_14") (pintype "unspecified"))
      (node (ref "KEY3") (pin "2") (pinfunction "2_2") (pintype "input"))
      (node (ref "U1") (pin "18") (pinfunction "PB0_18") (pintype "unspecified"))
    )
    (net (code "28") (name "/PB1_KEY1") (class "Default")
      (node (ref "H8") (pin "15") (pinfunction "15_15") (pintype "unspecified"))
      (node (ref "KEY4") (pin "2") (pinfunction "2_2") (pintype "input"))
      (node (ref "U1") (pin "19") (pinfunction "PB1_19") (pintype "unspecified"))
    )
    (net (code "29") (name "/PB3_D0") (class "Default")
      (node (ref "H7") (pin "3") (pinfunction "3_3") (pintype "unspecified"))
      (node (ref "H9") (pin "8") (pinfunction "8_8") (pintype "unspecified"))
      (node (ref "U1") (pin "39") (pinfunction "PB3_39") (pintype "unspecified"))
    )
    (net (code "30") (name "/PB4_D1") (class "Default")
      (node (ref "H7") (pin "4") (pinfunction "4_4") (pintype "unspecified"))
      (node (ref "H9") (pin "7") (pinfunction "7_7") (pintype "unspecified"))
      (node (ref "U1") (pin "40") (pinfunction "PB4_40") (pintype "unspecified"))
    )
    (net (code "31") (name "/PB6_DC") (class "Default")
      (node (ref "H7") (pin "6") (pinfunction "6_6") (pintype "unspecified"))
      (node (ref "H9") (pin "6") (pinfunction "6_6") (pintype "unspecified"))
      (node (ref "U1") (pin "42") (pinfunction "PB6_42") (pintype "unspecified"))
    )
    (net (code "32") (name "/PB7_CS") (class "Default")
      (node (ref "H7") (pin "7") (pinfunction "7_7") (pintype "unspecified"))
      (node (ref "H9") (pin "5") (pinfunction "5_5") (pintype "unspecified"))
      (node (ref "U1") (pin "43") (pinfunction "PB7_43") (pintype "unspecified"))
    )
    (net (code "33") (name "/PB8") (class "Default")
      (node (ref "H9") (pin "4") (pinfunction "4_4") (pintype "unspecified"))
      (node (ref "U1") (pin "45") (pinfunction "PB8_45") (pintype "unspecified"))
    )
    (net (code "34") (name "/PB9") (class "Default")
      (node (ref "H9") (pin "3") (pinfunction "3_3") (pintype "unspecified"))
      (node (ref "U1") (pin "46") (pinfunction "PB9_46") (pintype "unspecified"))
    )
    (net (code "35") (name "/PB10") (class "Default")
      (node (ref "H8") (pin "16") (pinfunction "16_16") (pintype "unspecified"))
      (node (ref "U1") (pin "21") (pinfunction "PB10_21") (pintype "unspecified"))
    )
    (net (code "36") (name "/PB11") (class "Default")
      (node (ref "H8") (pin "17") (pinfunction "17_17") (pintype "unspecified"))
      (node (ref "U1") (pin "22") (pinfunction "PB11_22") (pintype "unspecified"))
    )
    (net (code "37") (name "/PB12") (class "Default")
      (node (ref "H9") (pin "17") (pinfunction "17_17") (pintype "unspecified"))
      (node (ref "U1") (pin "25") (pinfunction "PB12_25") (pintype "unspecified"))
    )
    (net (code "38") (name "/PB13") (class "Default")
      (node (ref "H9") (pin "16") (pinfunction "16_16") (pintype "unspecified"))
      (node (ref "U1") (pin "26") (pinfunction "PB13_26") (pintype "unspecified"))
    )
    (net (code "39") (name "/PB14") (class "Default")
      (node (ref "H9") (pin "15") (pinfunction "15_15") (pintype "unspecified"))
      (node (ref "U1") (pin "27") (pinfunction "PB14_27") (pintype "unspecified"))
    )
    (net (code "40") (name "/PB15") (class "Default")
      (node (ref "H9") (pin "14") (pinfunction "14_14") (pintype "unspecified"))
      (node (ref "U1") (pin "28") (pinfunction "PB15_28") (pintype "unspecified"))
    )
    (net (code "41") (name "/PC13") (class "Default")
      (node (ref "H8") (pin "1") (pinfunction "1_1") (pintype "unspecified"))
      (node (ref "U1") (pin "2") (pinfunction "PC13-TAMPER-RTC_2") (pintype "unspecified"))
    )
    (net (code "42") (name "/PC14_32.768") (class "Default")
      (node (ref "C13") (pin "2") (pinfunction "2_2") (pintype "input"))
      (node (ref "H8") (pin "3") (pinfunction "3_3") (pintype "unspecified"))
      (node (ref "U1") (pin "3") (pinfunction "PC14-OSC32_IN_3") (pintype "unspecified"))
      (node (ref "X3") (pin "1") (pinfunction "OE#_1") (pintype "input"))
    )
    (net (code "43") (name "/PC15_32.768") (class "Default")
      (node (ref "C12") (pin "2") (pinfunction "2_2") (pintype "input"))
      (node (ref "H8") (pin "2") (pinfunction "2_2") (pintype "unspecified"))
      (node (ref "U1") (pin "4") (pinfunction "PC15-OSC32_OUT_4") (pintype "unspecified"))
      (node (ref "X3") (pin "4") (pinfunction "OUT_4") (pintype "input"))
    )
    (net (code "44") (name "/RESET") (class "Default")
      (node (ref "C11") (pin "1") (pinfunction "1_1") (pintype "input"))
      (node (ref "KEY1") (pin "1") (pinfunction "1_1") (pintype "input"))
      (node (ref "R7") (pin "1") (pinfunction "1_1") (pintype "input"))
      (node (ref "U1") (pin "7") (pinfunction "NRST_7") (pintype "unspecified"))
    )
    (net (code "45") (name "/SWCLK") (class "Default")
      (node (ref "H1") (pin "3") (pinfunction "3_3") (pintype "unspecified"))
      (node (ref "R5") (pin "2") (pinfunction "2_2") (pintype "input"))
      (node (ref "U1") (pin "37") (pinfunction "PA14_37") (pintype "unspecified"))
    )
    (net (code "46") (name "/SWDIO") (class "Default")
      (node (ref "H1") (pin "2") (pinfunction "2_2") (pintype "unspecified"))
      (node (ref "R6") (pin "1") (pinfunction "1_1") (pintype "input"))
      (node (ref "U1") (pin "34") (pinfunction "PA13_34") (pintype "unspecified"))
    )
    (net (code "47") (name "GND") (class "Default")
      (node (ref "C1") (pin "1") (pinfunction "1_1") (pintype "unspecified"))
      (node (ref "C11") (pin "2") (pinfunction "2_2") (pintype "input"))
      (node (ref "C12") (pin "1") (pinfunction "1_1") (pintype "input"))
      (node (ref "C13") (pin "1") (pinfunction "1_1") (pintype "input"))
      (node (ref "C14") (pin "1") (pinfunction "1_1") (pintype "input"))
      (node (ref "C15") (pin "1") (pinfunction "1_1") (pintype "input"))
      (node (ref "C16") (pin "2") (pinfunction "2_2") (pintype "input"))
      (node (ref "C2") (pin "1") (pinfunction "1_1") (pintype "input"))
      (node (ref "C3") (pin "1") (pinfunction "1_1") (pintype "unspecified"))
      (node (ref "C4") (pin "1") (pinfunction "1_1") (pintype "input"))
      (node (ref "C7") (pin "2") (pinfunction "2_2") (pintype "unspecified"))
      (node (ref "C8") (pin "2") (pinfunction "2_2") (pintype "unspecified"))
      (node (ref "CN1") (pin "5") (pinfunction "5_5") (pintype "unspecified"))
      (node (ref "CN1") (pin "6") (pinfunction "6_6") (pintype "unspecified"))
      (node (ref "H1") (pin "4") (pinfunction "4_4") (pintype "unspecified"))
      (node (ref "H7") (pin "1") (pinfunction "1_1") (pintype "unspecified"))
      (node (ref "H8") (pin "4") (pinfunction "4_4") (pintype "unspecified"))
      (node (ref "H9") (pin "2") (pinfunction "2_2") (pintype "unspecified"))
      (node (ref "KEY1") (pin "2") (pinfunction "2_2") (pintype "input"))
      (node (ref "KEY3") (pin "1") (pinfunction "1_1") (pintype "input"))
      (node (ref "KEY4") (pin "1") (pinfunction "1_1") (pintype "input"))
      (node (ref "R1") (pin "2") (pinfunction "2_2") (pintype "input"))
      (node (ref "R13") (pin "2") (pinfunction "2_2") (pintype "input"))
      (node (ref "R5") (pin "1") (pinfunction "1_1") (pintype "input"))
      (node (ref "U1") (pin "23") (pinfunction "VSS_1_23") (pintype "unspecified"))
      (node (ref "U1") (pin "35") (pinfunction "VSS_2_35") (pintype "unspecified"))
      (node (ref "U1") (pin "47") (pinfunction "VSS_3_47") (pintype "unspecified"))
      (node (ref "U1") (pin "8") (pinfunction "VSSA_8") (pintype "unspecified"))
      (node (ref "U10") (pin "4") (pinfunction "GND_4") (pintype "unspecified"))
      (node (ref "U13") (pin "2") (pinfunction "2_2") (pintype "unspecified"))
      (node (ref "U14") (pin "2") (pinfunction "2_2") (pintype "unspecified"))
      (node (ref "U18") (pin "2") (pinfunction "2_2") (pintype "unspecified"))
      (node (ref "U19") (pin "1") (pinfunction "1_1") (pintype "unspecified"))
      (node (ref "U2") (pin "2") (pinfunction "VSS_2") (pintype "unspecified"))
      (node (ref "U20") (pin "1") (pinfunction "1_1") (pintype "unspecified"))
      (node (ref "U22") (pin "1") (pinfunction "1_1") (pintype "unspecified"))
      (node (ref "U23") (pin "2") (pinfunction "-_2") (pintype "unspecified"))
      (node (ref "U24") (pin "2") (pinfunction "2_2") (pintype "unspecified"))
      (node (ref "U25") (pin "1") (pinfunction "1_1") (pintype "unspecified"))
      (node (ref "U26") (pin "1") (pinfunction "1_1") (pintype "unspecified"))
      (node (ref "U27") (pin "2") (pinfunction "2_2") (pintype "unspecified"))
      (node (ref "U28") (pin "2") (pinfunction "2_2") (pintype "unspecified"))
      (node (ref "U9") (pin "10") (pinfunction "PGND2_10") (pintype "unspecified"))
      (node (ref "U9") (pin "18") (pinfunction "GND_18") (pintype "unspecified"))
      (node (ref "U9") (pin "3") (pinfunction "PGND1_3") (pintype "unspecified"))
      (node (ref "U9") (pin "4") (pinfunction "PGND1_4") (pintype "unspecified"))
      (node (ref "U9") (pin "9") (pinfunction "PGND2_9") (pintype "unspecified"))
      (node (ref "USB1") (pin "5") (pinfunction "GND_5") (pintype "input"))
      (node (ref "X3") (pin "2") (pinfunction "GND_2") (pintype "input"))
      (node (ref "X3") (pin "3") (pinfunction "GND_3") (pintype "input"))
    )
    (net (code "48") (name "Net-(CN1-Pad3)") (class "Default")
      (node (ref "CN1") (pin "3") (pinfunction "3_3") (pintype "unspecified"))
      (node (ref "R3") (pin "2") (pinfunction "2_2") (pintype "input"))
    )
    (net (code "49") (name "Net-(CN1-Pad4)") (class "Default")
      (node (ref "CN1") (pin "4") (pinfunction "4_4") (pintype "unspecified"))
      (node (ref "R4") (pin "1") (pinfunction "1_1") (pintype "input"))
    )
    (net (code "50") (name "Net-(LED1-C)") (class "Default")
      (node (ref "LED1") (pin "1") (pinfunction "C_1") (pintype "input"))
      (node (ref "R1") (pin "1") (pinfunction "1_1") (pintype "input"))
    )
    (net (code "51") (name "Net-(USB1-D+)") (class "Default")
      (node (ref "R9") (pin "1") (pinfunction "1_1") (pintype "input"))
      (node (ref "USB1") (pin "3") (pinfunction "D+_3") (pintype "input"))
    )
    (net (code "52") (name "Net-(USB1-D-)") (class "Default")
      (node (ref "R8") (pin "1") (pinfunction "1_1") (pintype "input"))
      (node (ref "USB1") (pin "2") (pinfunction "D-_2") (pintype "input"))
    )
    (net (code "53") (name "VCC3V3") (class "Default")
      (node (ref "C14") (pin "2") (pinfunction "2_2") (pintype "input"))
      (node (ref "C3") (pin "2") (pinfunction "2_2") (pintype "unspecified"))
      (node (ref "C4") (pin "2") (pinfunction "2_2") (pintype "input"))
      (node (ref "CN1") (pin "1") (pinfunction "1_1") (pintype "unspecified"))
      (node (ref "CN1") (pin "2") (pinfunction "2_2") (pintype "unspecified"))
      (node (ref "H1") (pin "1") (pinfunction "1_1") (pintype "unspecified"))
      (node (ref "H7") (pin "2") (pinfunction "2_2") (pintype "unspecified"))
      (node (ref "H8") (pin "5") (pinfunction "5_5") (pintype "unspecified"))
      (node (ref "H9") (pin "1") (pinfunction "1_1") (pintype "unspecified"))
      (node (ref "KEY2") (pin "1") (pinfunction "1_1") (pintype "input"))
      (node (ref "LED1") (pin "2") (pinfunction "A_2") (pintype "input"))
      (node (ref "R10") (pin "1") (pinfunction "1_1") (pintype "input"))
      (node (ref "R14") (pin "2") (pinfunction "2_2") (pintype "input"))
      (node (ref "R6") (pin "2") (pinfunction "2_2") (pintype "input"))
      (node (ref "R7") (pin "2") (pinfunction "2_2") (pintype "input"))
      (node (ref "U1") (pin "24") (pinfunction "VDD_1_24") (pintype "unspecified"))
      (node (ref "U1") (pin "36") (pinfunction "VDD_2_36") (pintype "unspecified"))
      (node (ref "U1") (pin "48") (pinfunction "VDD_3_48") (pintype "unspecified"))
      (node (ref "U1") (pin "9") (pinfunction "VDDA_9") (pintype "unspecified"))
      (node (ref "U10") (pin "1") (pinfunction "VDD_1") (pintype "unspecified"))
      (node (ref "U14") (pin "1") (pinfunction "1_1") (pintype "unspecified"))
      (node (ref "U18") (pin "1") (pinfunction "1_1") (pintype "unspecified"))
      (node (ref "U19") (pin "2") (pinfunction "2_2") (pintype "unspecified"))
      (node (ref "U2") (pin "5") (pinfunction "VOUT_5") (pintype "unspecified"))
      (node (ref "U20") (pin "2") (pinfunction "2_2") (pintype "unspecified"))
      (node (ref "U25") (pin "2") (pinfunction "2_2") (pintype "unspecified"))
      (node (ref "U26") (pin "2") (pinfunction "2_2") (pintype "unspecified"))
      (node (ref "U27") (pin "1") (pinfunction "1_1") (pintype "unspecified"))
      (node (ref "U28") (pin "1") (pinfunction "1_1") (pintype "unspecified"))
      (node (ref "U9") (pin "20") (pinfunction "VCC_20") (pintype "unspecified"))
    )
    (net (code "54") (name "VCC_BAT") (class "Default")
      (node (ref "U1") (pin "1") (pinfunction "VBAT_1") (pintype "unspecified"))
      (node (ref "U13") (pin "1") (pinfunction "1_1") (pintype "unspecified"))
      (node (ref "U23") (pin "1") (pinfunction "+_1") (pintype "unspecified"))
      (node (ref "U24") (pin "1") (pinfunction "1_1") (pintype "unspecified"))
    )
    (net (code "55") (name "unconnected-(U2-NC-Pad4)") (class "Default")
      (node (ref "U2") (pin "4") (pinfunction "NC_4") (pintype "unspecified+no_connect"))
    )
    (net (code "56") (name "unconnected-(U10-NC-Pad3)") (class "Default")
      (node (ref "U10") (pin "3") (pinfunction "NC_3") (pintype "unspecified+no_connect"))
    )
    (net (code "57") (name "unconnected-(USB1-EH-Pad6)") (class "Default")
      (node (ref "USB1") (pin "6") (pinfunction "EH_6") (pintype "input+no_connect"))
    )
    (net (code "58") (name "unconnected-(USB1-ID-Pad4)") (class "Default")
      (node (ref "USB1") (pin "4") (pinfunction "ID_4") (pintype "input+no_connect"))
    )
  )
)
